# OZ440-SE100-CAR003_sheet10.net
KiCad netlist of a schematic drawn in Altium Designer
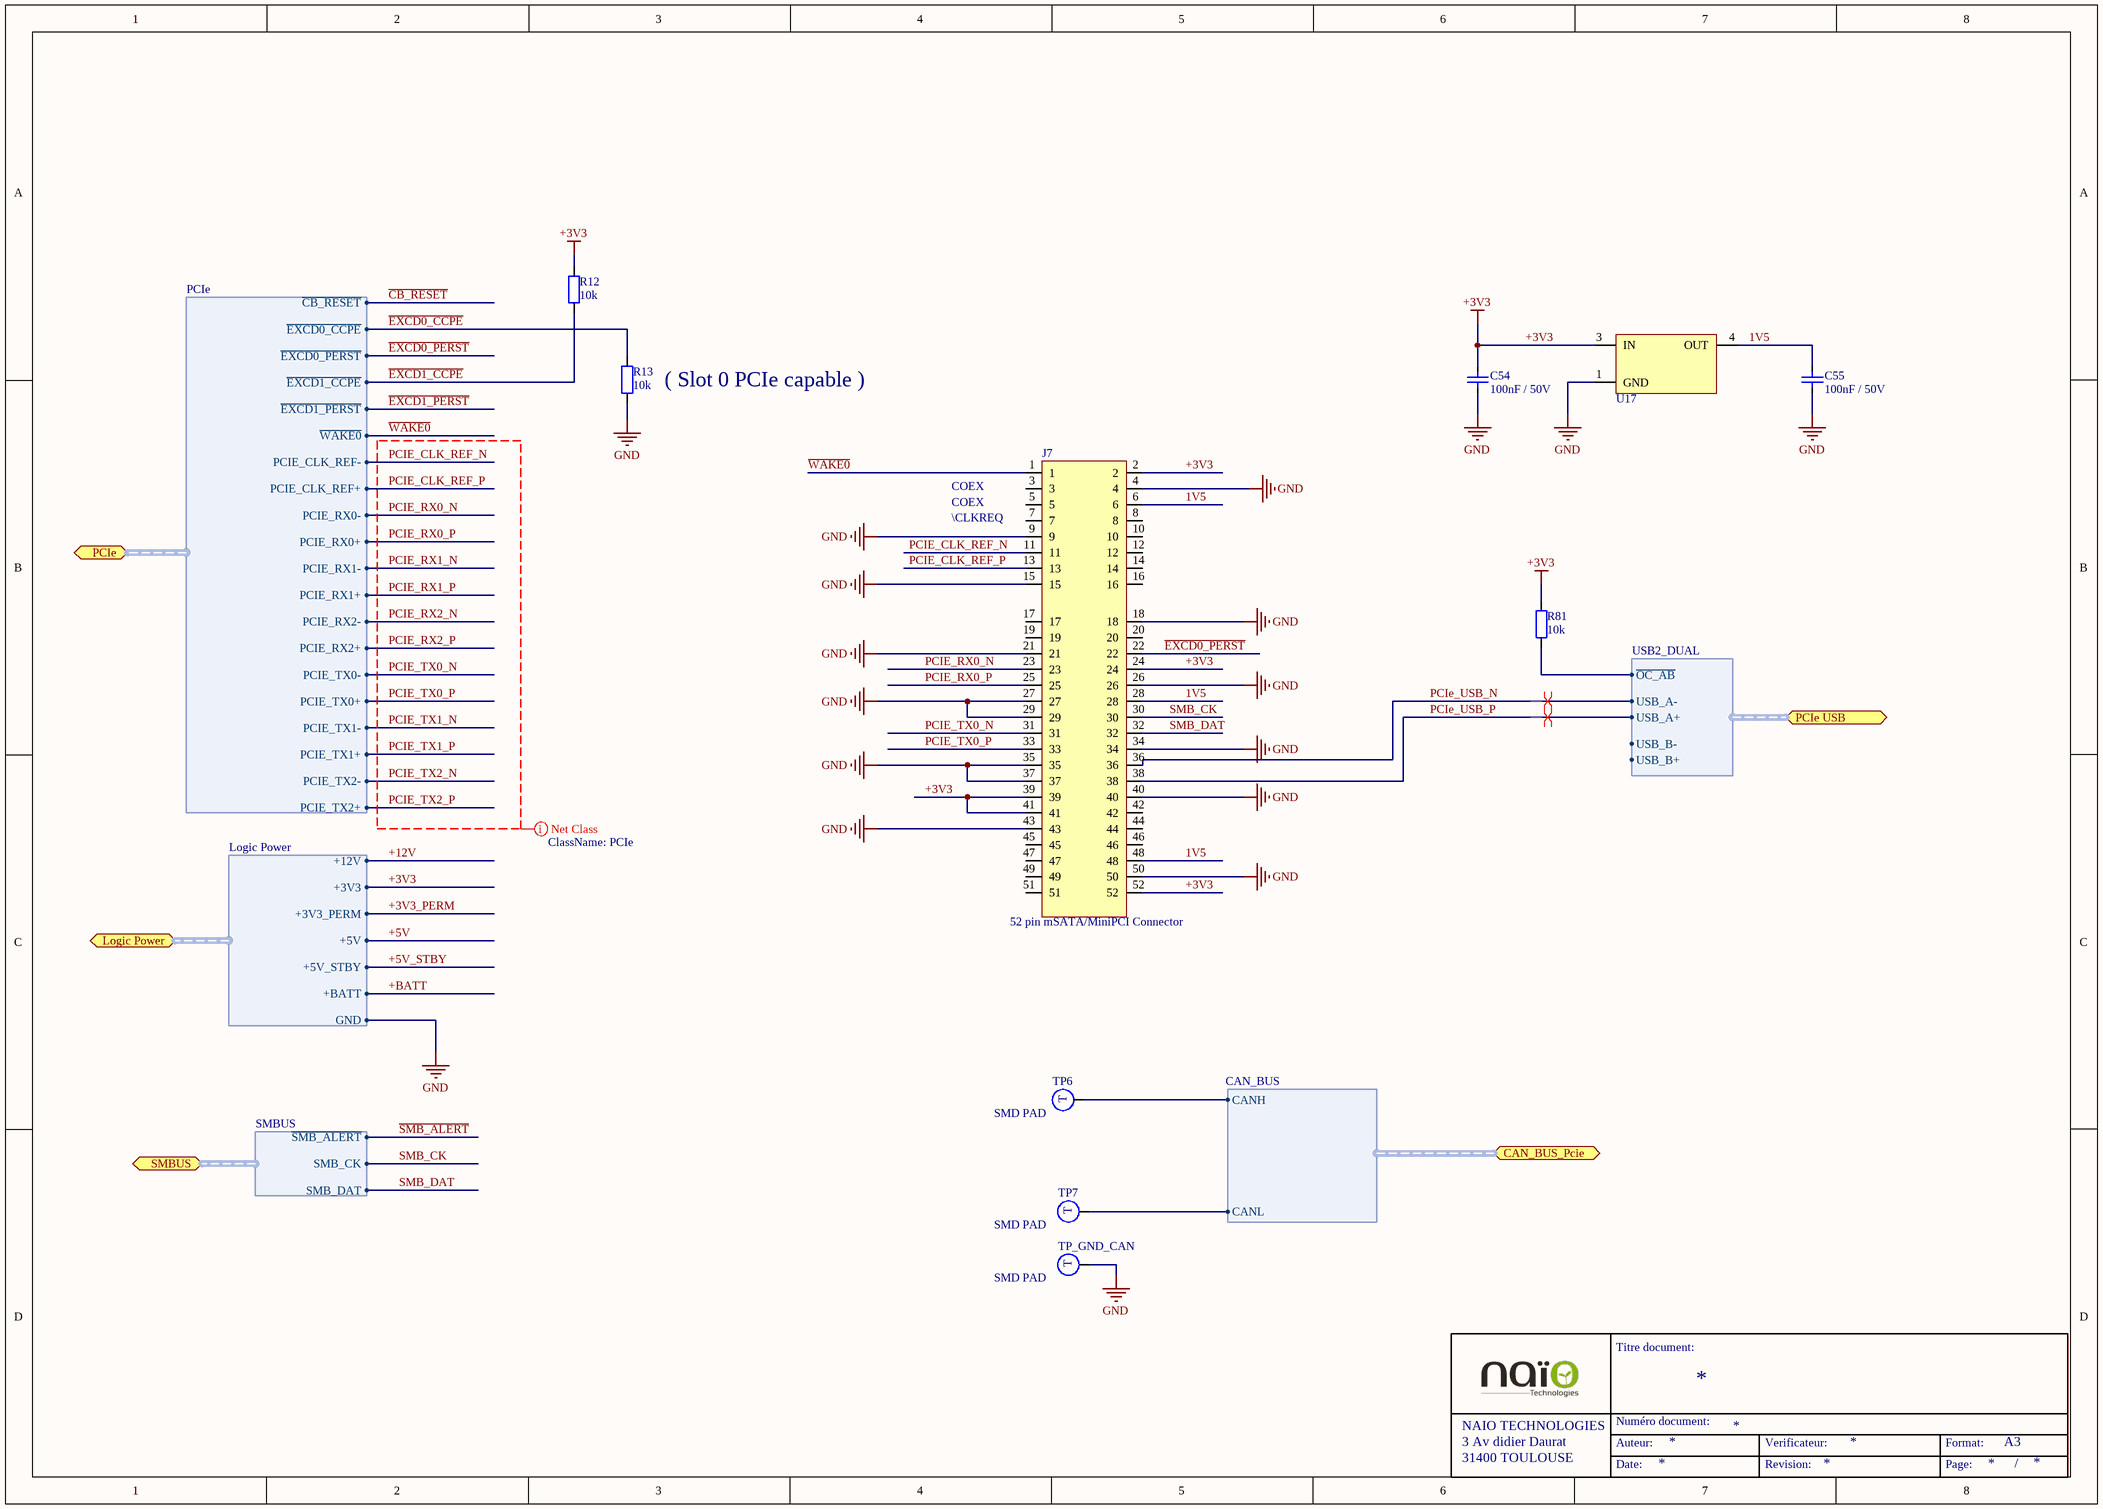
[diagram p0: OZ440-SE100-CAR003_sheet10.SchDoc]

(export (version "E")
  (design (tool "Eeschema 10.0.6"))
  (components
    (comp (ref "C54")
      (value "CAP-SMD")
      (footprint "C0805-STD")
      (description "0805 100nF / 50V  X7R ceramic capacitor")
      (fields
        (field (name "DISPLAYED REFERENCE") "100nF / 50V")
        (field (name "TOLERANCE") "+/- 10%")
        (field (name "MANUFACTURER") "vishay")
      )
      (libsource (lib "lib_NAIO") (part "CAP-SMD"))
    )
    (comp (ref "C55")
      (value "CAP-SMD")
      (footprint "C0805-STD")
      (description "0805 100nF / 50V  X7R ceramic capacitor")
      (fields
        (field (name "DISPLAYED REFERENCE") "100nF / 50V")
        (field (name "TOLERANCE") "+/- 10%")
        (field (name "MANUFACTURER") "vishay")
      )
      (libsource (lib "lib_NAIO") (part "CAP-SMD"))
    )
    (comp (ref "J7")
      (value "CONN-STD-miniPCI_msata")
      (footprint "CONN-SPE_MiniPCI-mSATA_MOLEX_67910-0002")
      (description "miniPCI / mSATA connector")
      (fields
        (field (name "DISPLAYED REFERENCE") "52 pin mSATA/MiniPCI Connector")
        (field (name "MANUFACTURER") "MOLEX")
      )
      (libsource (lib "lib_NAIO") (part "CONN-STD-miniPCI_msata"))
    )
    (comp (ref "R12")
      (value "RES-SMD")
      (footprint "R0805-STD")
      (description "10k Ohm 0805 SMD resistor")
      (fields
        (field (name "DISPLAYED REFERENCE") "10k")
        (field (name "TOLERANCE") "1 %")
        (field (name "MANUFACTURER") "Vishay")
      )
      (libsource (lib "lib_NAIO") (part "RES-SMD"))
    )
    (comp (ref "R13")
      (value "RES-SMD")
      (footprint "R0805-STD")
      (description "10k Ohm 0805 SMD resistor")
      (fields
        (field (name "DISPLAYED REFERENCE") "10k")
        (field (name "TOLERANCE") "1 %")
        (field (name "MANUFACTURER") "Vishay")
      )
      (libsource (lib "lib_NAIO") (part "RES-SMD"))
    )
    (comp (ref "R81")
      (value "RES-SMD")
      (footprint "R0805-STD")
      (description "10k Ohm 0805 SMD resistor")
      (fields
        (field (name "DISPLAYED REFERENCE") "10k")
        (field (name "TOLERANCE") "1 %")
        (field (name "MANUFACTURER") "Vishay")
      )
      (libsource (lib "lib_NAIO") (part "RES-SMD"))
    )
    (comp (ref "TP6")
      (value "TP-STD-TEST_POINT")
      (footprint "MEC-STD-SMD_PAD_2mm")
      (description "SMD Pad for wire soldering")
      (fields (field (name "DISPLAYED REFERENCE") "SMD PAD"))
      (libsource (lib "lib_NAIO") (part "TP-STD-TEST_POINT"))
    )
    (comp (ref "TP7")
      (value "TP-STD-TEST_POINT")
      (footprint "MEC-STD-SMD_PAD_2mm")
      (description "SMD Pad for wire soldering")
      (fields (field (name "DISPLAYED REFERENCE") "SMD PAD"))
      (libsource (lib "lib_NAIO") (part "TP-STD-TEST_POINT"))
    )
    (comp (ref "TP_GND_CAN")
      (value "TP-STD-TEST_POINT")
      (footprint "MEC-STD-SMD_PAD_2mm")
      (description "SMD Pad for wire soldering")
      (fields (field (name "DISPLAYED REFERENCE") "SMD PAD"))
      (libsource (lib "lib_NAIO") (part "TP-STD-TEST_POINT"))
    )
    (comp (ref "U17")
      (value "NCP1117-DPAK")
      (footprint "DPAK-STD")
      (description "1.0 A Low-Dropout Positive Voltage Regulators")
      (fields (field (name "MANUFACTURER") "On semi"))
      (libsource (lib "lib_NAIO") (part "NCP1117-DPAK"))
    )
  )
  (nets
    (net (code "7") (name "+3V3") (class "Default")
      (node (ref "C54") (pin "2") (pinfunction "2_2") (pintype "passive"))
      (node (ref "J7") (pin "2") (pinfunction "2_2") (pintype "passive"))
      (node (ref "J7") (pin "24") (pinfunction "24_24") (pintype "passive"))
      (node (ref "J7") (pin "39") (pinfunction "39_39") (pintype "passive"))
      (node (ref "J7") (pin "41") (pinfunction "41_41") (pintype "passive"))
      (node (ref "J7") (pin "52") (pinfunction "52_52") (pintype "passive"))
      (node (ref "R12") (pin "1") (pinfunction "1_1") (pintype "passive"))
      (node (ref "R81") (pin "1") (pinfunction "1_1") (pintype "passive"))
      (node (ref "U17") (pin "3") (pinfunction "IN_3") (pintype "passive"))
    )
    (net (code "13") (name "/1V5") (class "Default")
      (node (ref "C55") (pin "2") (pinfunction "2_2") (pintype "passive"))
      (node (ref "J7") (pin "28") (pinfunction "28_28") (pintype "passive"))
      (node (ref "J7") (pin "48") (pinfunction "48_48") (pintype "passive"))
      (node (ref "J7") (pin "6") (pinfunction "6_6") (pintype "passive"))
      (node (ref "U17") (pin "4") (pinfunction "OUT_4") (pintype "passive"))
    )
    (net (code "14") (name "/CANH") (class "Default")
      (node (ref "TP6") (pin "1") (pinfunction "T_1") (pintype "passive"))
    )
    (net (code "15") (name "/CANL") (class "Default")
      (node (ref "TP7") (pin "1") (pinfunction "T_1") (pintype "passive"))
    )
    (net (code "17") (name "/EXCD0_CCPE") (class "Default")
      (node (ref "R13") (pin "1") (pinfunction "1_1") (pintype "passive"))
    )
    (net (code "18") (name "/EXCD0_PERST") (class "Default")
      (node (ref "J7") (pin "22") (pinfunction "22_22") (pintype "passive"))
    )
    (net (code "19") (name "/EXCD1_CCPE") (class "Default")
      (node (ref "R12") (pin "2") (pinfunction "2_2") (pintype "passive"))
    )
    (net (code "21") (name "/PCIE_CLK_REF_N") (class "Default")
      (node (ref "J7") (pin "11") (pinfunction "11_11") (pintype "passive"))
    )
    (net (code "22") (name "/PCIE_CLK_REF_P") (class "Default")
      (node (ref "J7") (pin "13") (pinfunction "13_13") (pintype "passive"))
    )
    (net (code "23") (name "/PCIE_RX0_N") (class "Default")
      (node (ref "J7") (pin "23") (pinfunction "23_23") (pintype "passive"))
    )
    (net (code "24") (name "/PCIE_RX0_P") (class "Default")
      (node (ref "J7") (pin "25") (pinfunction "25_25") (pintype "passive"))
    )
    (net (code "29") (name "/PCIE_TX0_N") (class "Default")
      (node (ref "J7") (pin "31") (pinfunction "31_31") (pintype "passive"))
    )
    (net (code "30") (name "/PCIE_TX0_P") (class "Default")
      (node (ref "J7") (pin "33") (pinfunction "33_33") (pintype "passive"))
    )
    (net (code "35") (name "/PCIe_USB_N") (class "Default")
      (node (ref "J7") (pin "36") (pinfunction "36_36") (pintype "passive"))
    )
    (net (code "36") (name "/PCIe_USB_P") (class "Default")
      (node (ref "J7") (pin "38") (pinfunction "38_38") (pintype "passive"))
    )
    (net (code "38") (name "/SMB_CK") (class "Default")
      (node (ref "J7") (pin "30") (pinfunction "30_30") (pintype "passive"))
    )
    (net (code "39") (name "/SMB_DAT") (class "Default")
      (node (ref "J7") (pin "32") (pinfunction "32_32") (pintype "passive"))
    )
    (net (code "40") (name "/WAKE0") (class "Default")
      (node (ref "J7") (pin "1") (pinfunction "1_1") (pintype "passive"))
    )
    (net (code "46") (name "/~{OC_AB}") (class "Default")
      (node (ref "R81") (pin "2") (pinfunction "2_2") (pintype "passive"))
    )
    (net (code "47") (name "GND") (class "Default")
      (node (ref "C54") (pin "1") (pinfunction "1_1") (pintype "passive"))
      (node (ref "C55") (pin "1") (pinfunction "1_1") (pintype "passive"))
      (node (ref "J7") (pin "15") (pinfunction "15_15") (pintype "passive"))
      (node (ref "J7") (pin "18") (pinfunction "18_18") (pintype "passive"))
      (node (ref "J7") (pin "21") (pinfunction "21_21") (pintype "passive"))
      (node (ref "J7") (pin "26") (pinfunction "26_26") (pintype "passive"))
      (node (ref "J7") (pin "27") (pinfunction "27_27") (pintype "passive"))
      (node (ref "J7") (pin "29") (pinfunction "29_29") (pintype "passive"))
      (node (ref "J7") (pin "34") (pinfunction "34_34") (pintype "passive"))
      (node (ref "J7") (pin "35") (pinfunction "35_35") (pintype "passive"))
      (node (ref "J7") (pin "37") (pinfunction "37_37") (pintype "passive"))
      (node (ref "J7") (pin "4") (pinfunction "4_4") (pintype "passive"))
      (node (ref "J7") (pin "40") (pinfunction "40_40") (pintype "passive"))
      (node (ref "J7") (pin "43") (pinfunction "43_43") (pintype "passive"))
      (node (ref "J7") (pin "50") (pinfunction "50_50") (pintype "passive"))
      (node (ref "J7") (pin "9") (pinfunction "9_9") (pintype "passive"))
      (node (ref "R13") (pin "2") (pinfunction "2_2") (pintype "passive"))
      (node (ref "TP_GND_CAN") (pin "1") (pinfunction "T_1") (pintype "passive"))
      (node (ref "U17") (pin "1") (pinfunction "GND_1") (pintype "passive"))
    )
    (net (code "48") (name "unconnected-(J7-Pad3)") (class "Default")
      (node (ref "J7") (pin "3") (pinfunction "3_3") (pintype "passive"))
    )
    (net (code "49") (name "unconnected-(J7-Pad5)") (class "Default")
      (node (ref "J7") (pin "5") (pinfunction "5_5") (pintype "passive"))
    )
    (net (code "50") (name "unconnected-(J7-Pad7)") (class "Default")
      (node (ref "J7") (pin "7") (pinfunction "7_7") (pintype "passive"))
    )
    (net (code "51") (name "unconnected-(J7-Pad8)") (class "Default")
      (node (ref "J7") (pin "8") (pinfunction "8_8") (pintype "passive"))
    )
    (net (code "52") (name "unconnected-(J7-Pad10)") (class "Default")
      (node (ref "J7") (pin "10") (pinfunction "10_10") (pintype "passive"))
    )
    (net (code "53") (name "unconnected-(J7-Pad12)") (class "Default")
      (node (ref "J7") (pin "12") (pinfunction "12_12") (pintype "passive"))
    )
    (net (code "54") (name "unconnected-(J7-Pad14)") (class "Default")
      (node (ref "J7") (pin "14") (pinfunction "14_14") (pintype "passive"))
    )
    (net (code "55") (name "unconnected-(J7-Pad16)") (class "Default")
      (node (ref "J7") (pin "16") (pinfunction "16_16") (pintype "passive"))
    )
    (net (code "56") (name "unconnected-(J7-Pad17)") (class "Default")
      (node (ref "J7") (pin "17") (pinfunction "17_17") (pintype "passive"))
    )
    (net (code "57") (name "unconnected-(J7-Pad19)") (class "Default")
      (node (ref "J7") (pin "19") (pinfunction "19_19") (pintype "passive"))
    )
    (net (code "58") (name "unconnected-(J7-Pad20)") (class "Default")
      (node (ref "J7") (pin "20") (pinfunction "20_20") (pintype "passive"))
    )
    (net (code "59") (name "unconnected-(J7-Pad42)") (class "Default")
      (node (ref "J7") (pin "42") (pinfunction "42_42") (pintype "passive"))
    )
    (net (code "60") (name "unconnected-(J7-Pad44)") (class "Default")
      (node (ref "J7") (pin "44") (pinfunction "44_44") (pintype "passive"))
    )
    (net (code "61") (name "unconnected-(J7-Pad45)") (class "Default")
      (node (ref "J7") (pin "45") (pinfunction "45_45") (pintype "passive"))
    )
    (net (code "62") (name "unconnected-(J7-Pad46)") (class "Default")
      (node (ref "J7") (pin "46") (pinfunction "46_46") (pintype "passive"))
    )
    (net (code "63") (name "unconnected-(J7-Pad47)") (class "Default")
      (node (ref "J7") (pin "47") (pinfunction "47_47") (pintype "passive"))
    )
    (net (code "64") (name "unconnected-(J7-Pad49)") (class "Default")
      (node (ref "J7") (pin "49") (pinfunction "49_49") (pintype "passive"))
    )
    (net (code "65") (name "unconnected-(J7-Pad51)") (class "Default")
      (node (ref "J7") (pin "51") (pinfunction "51_51") (pintype "passive"))
    )
  )
)
